# displays.net
KiCad netlist of a schematic drawn in Altium Designer
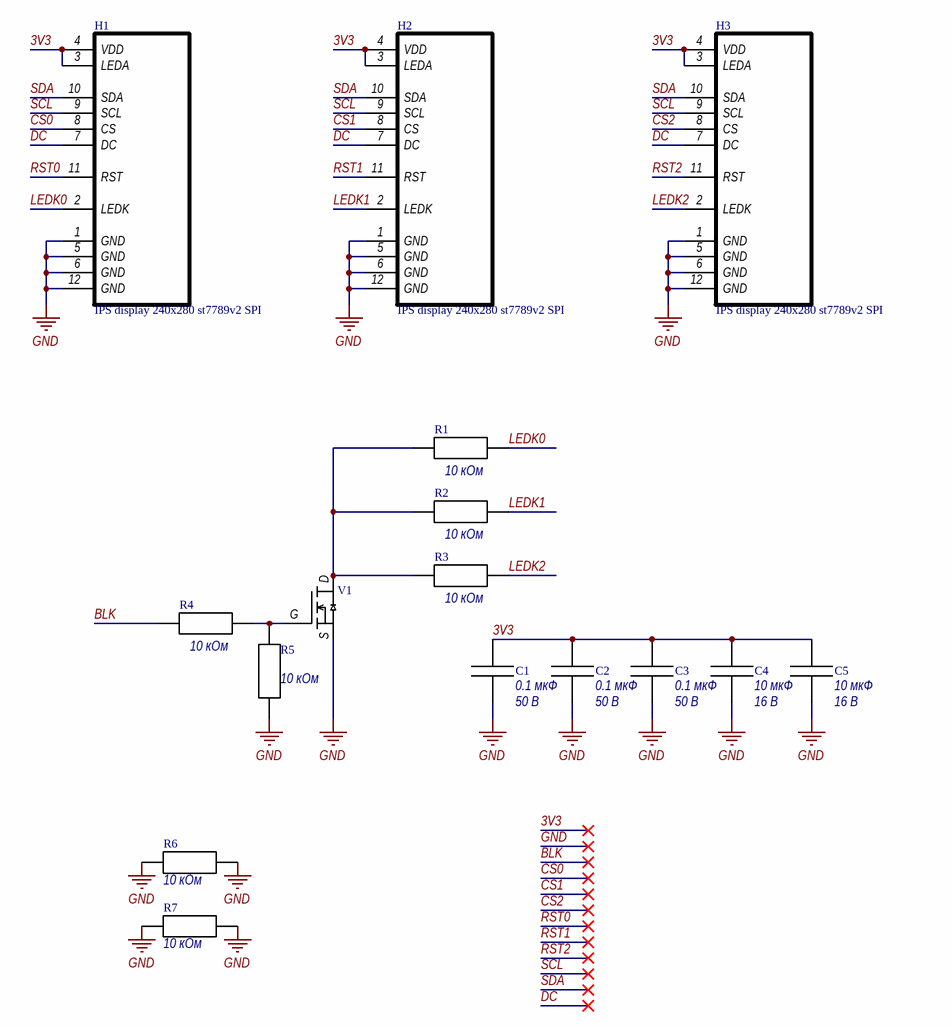
[diagram p0: displays.SchDoc]

(export (version "E")
  (design (tool "Eeschema 10.0.6"))
  (components
    (comp (ref "C1")
      (value "0.1 мкФ")
      (footprint "0805-CAP")
      (description "Конденсатор керамический, 0.1 мкФ, X7R, 50 В, точность 10%, 0805")
      (fields (field (name "VOLTAGE") "50 В") (field (name "Comment") "GRM21BR71H104K"))
      (libsource (lib "") (part "Component_1_1"))
    )
    (comp (ref "C2")
      (value "0.1 мкФ")
      (footprint "0805-CAP")
      (description "Конденсатор керамический, 0.1 мкФ, X7R, 50 В, точность 10%, 0805")
      (fields (field (name "VOLTAGE") "50 В") (field (name "Comment") "GRM21BR71H104K"))
      (libsource (lib "") (part "Component_1_1"))
    )
    (comp (ref "C3")
      (value "0.1 мкФ")
      (footprint "0805-CAP")
      (description "Конденсатор керамический, 0.1 мкФ, X7R, 50 В, точность 10%, 0805")
      (fields (field (name "VOLTAGE") "50 В") (field (name "Comment") "GRM21BR71H104K"))
      (libsource (lib "") (part "Component_1_1"))
    )
    (comp (ref "C4")
      (value "10 мкФ")
      (footprint "0805-CAP")
      (description "Конденсатор керамичеcкий, 10 мкФ, X5R, 16 В, точность 10%, 0805")
      (fields
        (field (name "VOLTAGE") "16 В")
        (field (name "MANUFACTURER") "Murata")
        (field (name "Comment") "GRM21BR61C106K")
      )
      (libsource (lib "") (part "Component_1_1"))
    )
    (comp (ref "C5")
      (value "10 мкФ")
      (footprint "0805-CAP")
      (description "Конденсатор керамичеcкий, 10 мкФ, X5R, 16 В, точность 10%, 0805")
      (fields
        (field (name "VOLTAGE") "16 В")
        (field (name "MANUFACTURER") "Murata")
        (field (name "Comment") "GRM21BR61C106K")
      )
      (libsource (lib "") (part "Component_1_1"))
    )
    (comp (ref "H1")
      (value "IPS display 240x280 st7789v2 SPI")
      (footprint "(Требует доработки) IPS display 240x280 st7789v2 SPI")
      (description "Дисплей цветной, 1.69 дюйма, 240 x 280 точки, IPS, LH169T-IG01")
      (fields (field (name "MANUFACTURER") "NA"))
      (libsource (lib "Altium Vault") (part "IPS display 240x280 st7789v2 SPI"))
    )
    (comp (ref "H2")
      (value "IPS display 240x280 st7789v2 SPI")
      (footprint "(Требует доработки) IPS display 240x280 st7789v2 SPI")
      (description "Дисплей цветной, 1.69 дюйма, 240 x 280 точки, IPS, LH169T-IG01")
      (fields (field (name "MANUFACTURER") "NA"))
      (libsource (lib "Altium Vault") (part "IPS display 240x280 st7789v2 SPI"))
    )
    (comp (ref "H3")
      (value "IPS display 240x280 st7789v2 SPI")
      (footprint "(Требует доработки) IPS display 240x280 st7789v2 SPI")
      (description "Дисплей цветной, 1.69 дюйма, 240 x 280 точки, IPS, LH169T-IG01")
      (fields (field (name "MANUFACTURER") "NA"))
      (libsource (lib "Altium Vault") (part "IPS display 240x280 st7789v2 SPI"))
    )
    (comp (ref "R1")
      (value "10 кОм")
      (footprint "0805-RES")
      (description "Резистор, 10 кОм, 0.125 Вт, точность 1%, 0805")
      (fields (field (name "Comment") "RC0805FR-0710KL"))
      (libsource (lib "Altium Vault") (part "CMP-0677-A.2"))
    )
    (comp (ref "R2")
      (value "10 кОм")
      (footprint "0805-RES")
      (description "Резистор, 10 кОм, 0.125 Вт, точность 1%, 0805")
      (fields (field (name "Comment") "RC0805FR-0710KL"))
      (libsource (lib "Altium Vault") (part "Component_1"))
    )
    (comp (ref "R3")
      (value "10 кОм")
      (footprint "0805-RES")
      (description "Резистор, 10 кОм, 0.125 Вт, точность 1%, 0805")
      (fields (field (name "Comment") "RC0805FR-0710KL"))
      (libsource (lib "Altium Vault") (part "Component_1"))
    )
    (comp (ref "R4")
      (value "10 кОм")
      (footprint "0805-RES")
      (description "Резистор, 10 кОм, 0.125 Вт, точность 1%, 0805")
      (fields (field (name "Comment") "RC0805FR-0710KL"))
      (libsource (lib "") (part "Component_1_2"))
    )
    (comp (ref "R5")
      (value "10 кОм")
      (footprint "0805-RES")
      (description "Резистор, 10 кОм, 0.125 Вт, точность 1%, 0805")
      (fields (field (name "Comment") "RC0805FR-0710KL"))
      (libsource (lib "") (part "Component_1_3"))
    )
    (comp (ref "R6")
      (value "10 кОм")
      (footprint "0805-RES")
      (description "Резистор, 10 кОм, 0.125 Вт, точность 1%, 0805")
      (fields (field (name "Comment") "RC0805FR-0710KL"))
      (libsource (lib "Altium Vault") (part "Component_1"))
    )
    (comp (ref "R7")
      (value "10 кОм")
      (footprint "0805-RES")
      (description "Резистор, 10 кОм, 0.125 Вт, точность 1%, 0805")
      (fields (field (name "Comment") "RC0805FR-0710KL"))
      (libsource (lib "Altium Vault") (part "Component_1"))
    )
    (comp (ref "V1")
      (value "IRLML2030TRPBF")
      (footprint "SOT-23-3")
      (description "N-канальный транзистор, 30 в, 100 мОм(10 в), 2.7 а")
      (fields (field (name "MANUFACTURER") "International Rectifier"))
      (libsource (lib "Altium Vault") (part "CMP-0630-A.1"))
    )
  )
  (nets
    (net (code "1") (name "/3V3") (class "Default")
      (node (ref "C1") (pin "2") (pinfunction "2_2") (pintype "passive"))
      (node (ref "C2") (pin "2") (pinfunction "2_2") (pintype "passive"))
      (node (ref "C3") (pin "2") (pinfunction "2_2") (pintype "passive"))
      (node (ref "C4") (pin "2") (pinfunction "2_2") (pintype "passive"))
      (node (ref "C5") (pin "2") (pinfunction "2_2") (pintype "passive"))
      (node (ref "H1") (pin "3") (pinfunction "LEDA_3") (pintype "passive"))
      (node (ref "H1") (pin "4") (pinfunction "VDD_4") (pintype "passive"))
      (node (ref "H2") (pin "3") (pinfunction "LEDA_3") (pintype "passive"))
      (node (ref "H2") (pin "4") (pinfunction "VDD_4") (pintype "passive"))
      (node (ref "H3") (pin "3") (pinfunction "LEDA_3") (pintype "passive"))
      (node (ref "H3") (pin "4") (pinfunction "VDD_4") (pintype "passive"))
    )
    (net (code "2") (name "/BLK") (class "Default")
      (node (ref "R4") (pin "1") (pinfunction "1_1") (pintype "passive"))
    )
    (net (code "3") (name "/CS0") (class "Default")
      (node (ref "H1") (pin "8") (pinfunction "CS_8") (pintype "passive"))
    )
    (net (code "4") (name "/CS1") (class "Default")
      (node (ref "H2") (pin "8") (pinfunction "CS_8") (pintype "passive+no_connect"))
    )
    (net (code "5") (name "/CS2") (class "Default")
      (node (ref "H3") (pin "8") (pinfunction "CS_8") (pintype "passive+no_connect"))
    )
    (net (code "6") (name "/DC") (class "Default")
      (node (ref "H1") (pin "7") (pinfunction "DC_7") (pintype "passive"))
      (node (ref "H2") (pin "7") (pinfunction "DC_7") (pintype "passive"))
      (node (ref "H3") (pin "7") (pinfunction "DC_7") (pintype "passive"))
    )
    (net (code "7") (name "/LEDK0") (class "Default")
      (node (ref "H1") (pin "2") (pinfunction "LEDK_2") (pintype "passive"))
      (node (ref "R1") (pin "1") (pinfunction "1_1") (pintype "passive"))
    )
    (net (code "8") (name "/LEDK1") (class "Default")
      (node (ref "H2") (pin "2") (pinfunction "LEDK_2") (pintype "passive"))
      (node (ref "R2") (pin "1") (pinfunction "1_1") (pintype "passive"))
    )
    (net (code "9") (name "/LEDK2") (class "Default")
      (node (ref "H3") (pin "2") (pinfunction "LEDK_2") (pintype "passive"))
      (node (ref "R3") (pin "1") (pinfunction "1_1") (pintype "passive"))
    )
    (net (code "10") (name "/RST0") (class "Default")
      (node (ref "H1") (pin "11") (pinfunction "RST_11") (pintype "passive"))
    )
    (net (code "11") (name "/RST1") (class "Default")
      (node (ref "H2") (pin "11") (pinfunction "RST_11") (pintype "passive+no_connect"))
    )
    (net (code "12") (name "/RST2") (class "Default")
      (node (ref "H3") (pin "11") (pinfunction "RST_11") (pintype "passive+no_connect"))
    )
    (net (code "13") (name "/SCL") (class "Default")
      (node (ref "H1") (pin "9") (pinfunction "SCL_9") (pintype "passive"))
      (node (ref "H2") (pin "9") (pinfunction "SCL_9") (pintype "passive"))
      (node (ref "H3") (pin "9") (pinfunction "SCL_9") (pintype "passive"))
    )
    (net (code "14") (name "/SDA") (class "Default")
      (node (ref "H1") (pin "10") (pinfunction "SDA_10") (pintype "passive"))
      (node (ref "H2") (pin "10") (pinfunction "SDA_10") (pintype "passive"))
      (node (ref "H3") (pin "10") (pinfunction "SDA_10") (pintype "passive"))
    )
    (net (code "15") (name "GND") (class "Default")
      (node (ref "C1") (pin "1") (pinfunction "1_1") (pintype "passive"))
      (node (ref "C2") (pin "1") (pinfunction "1_1") (pintype "passive"))
      (node (ref "C3") (pin "1") (pinfunction "1_1") (pintype "passive"))
      (node (ref "C4") (pin "1") (pinfunction "1_1") (pintype "passive"))
      (node (ref "C5") (pin "1") (pinfunction "1_1") (pintype "passive"))
      (node (ref "H1") (pin "1") (pinfunction "GND_1") (pintype "passive"))
      (node (ref "H1") (pin "12") (pinfunction "GND_12") (pintype "passive"))
      (node (ref "H1") (pin "5") (pinfunction "GND_5") (pintype "passive"))
      (node (ref "H1") (pin "6") (pinfunction "GND_6") (pintype "passive"))
      (node (ref "H2") (pin "1") (pinfunction "GND_1") (pintype "passive"))
      (node (ref "H2") (pin "12") (pinfunction "GND_12") (pintype "passive"))
      (node (ref "H2") (pin "5") (pinfunction "GND_5") (pintype "passive"))
      (node (ref "H2") (pin "6") (pinfunction "GND_6") (pintype "passive"))
      (node (ref "H3") (pin "1") (pinfunction "GND_1") (pintype "passive"))
      (node (ref "H3") (pin "12") (pinfunction "GND_12") (pintype "passive"))
      (node (ref "H3") (pin "5") (pinfunction "GND_5") (pintype "passive"))
      (node (ref "H3") (pin "6") (pinfunction "GND_6") (pintype "passive"))
      (node (ref "R5") (pin "1") (pinfunction "1_1") (pintype "passive"))
      (node (ref "R6") (pin "1") (pinfunction "1_1") (pintype "passive"))
      (node (ref "R6") (pin "2") (pinfunction "2_2") (pintype "passive"))
      (node (ref "R7") (pin "1") (pinfunction "1_1") (pintype "passive"))
      (node (ref "R7") (pin "2") (pinfunction "2_2") (pintype "passive"))
      (node (ref "V1") (pin "S") (pinfunction "S_S") (pintype "passive"))
    )
    (net (code "16") (name "Net-(R1-Pad2)") (class "Default")
      (node (ref "R1") (pin "2") (pinfunction "2_2") (pintype "passive"))
      (node (ref "R2") (pin "2") (pinfunction "2_2") (pintype "passive"))
      (node (ref "R3") (pin "2") (pinfunction "2_2") (pintype "passive"))
      (node (ref "V1") (pin "D") (pinfunction "D_D") (pintype "passive"))
    )
    (net (code "17") (name "Net-(R4-Pad2)") (class "Default")
      (node (ref "R4") (pin "2") (pinfunction "2_2") (pintype "passive"))
      (node (ref "R5") (pin "2") (pinfunction "2_2") (pintype "passive"))
      (node (ref "V1") (pin "G") (pinfunction "G_G") (pintype "passive"))
    )
  )
)
